# Double_Socket_NoPowersch.net
KiCad netlist of a schematic drawn in EAGLE
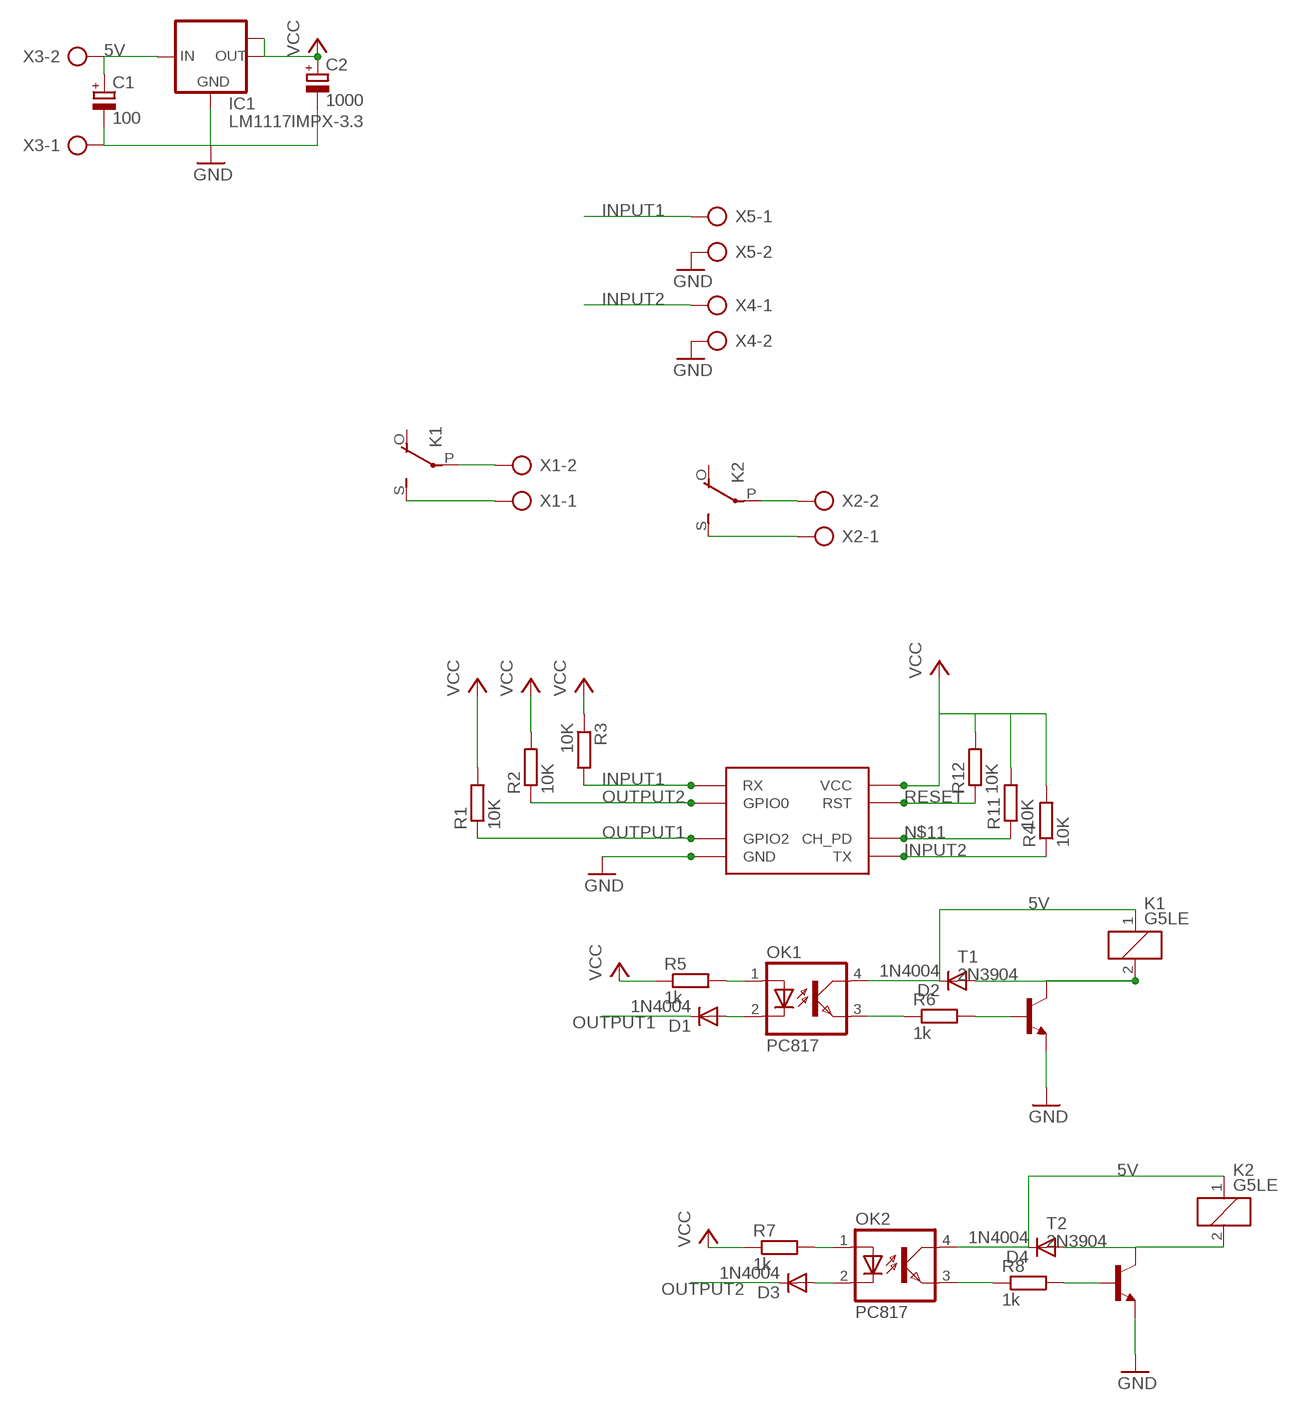
[diagram p0: schematic, sheet 1]

(export (version "E")
  (design (tool "Eeschema 10.0.6"))
  (components
    (comp (ref "C1")
      (value "100")
      (footprint "eagle-import:E5-10,5")
      (libsource (lib "eagle-import") (part "CPOL-EUE5-10.5"))
    )
    (comp (ref "C2")
      (value "1000")
      (footprint "eagle-import:E5-10,5")
      (libsource (lib "eagle-import") (part "CPOL-EUE5-10.5"))
    )
    (comp (ref "D1")
      (value "1N4004")
      (footprint "eagle-import:DO41-10")
      (libsource (lib "eagle-import") (part "1N4004"))
    )
    (comp (ref "D2")
      (value "1N4004")
      (footprint "eagle-import:DO41-10")
      (libsource (lib "eagle-import") (part "1N4004"))
    )
    (comp (ref "D3")
      (value "1N4004")
      (footprint "eagle-import:DO41-10")
      (libsource (lib "eagle-import") (part "1N4004"))
    )
    (comp (ref "D4")
      (value "1N4004")
      (footprint "eagle-import:DO41-10")
      (libsource (lib "eagle-import") (part "1N4004"))
    )
    (comp (ref "IC1")
      (value "LM1117IMPX-3.3")
      (footprint "eagle-import:SOT223")
      (libsource (lib "eagle-import") (part "LM1117IMPX-3.3"))
    )
    (comp (ref "K1")
      (value "G5LE")
      (footprint "eagle-import:G5LE")
      (libsource (lib "eagle-import") (part "G5LE"))
    )
    (comp (ref "K2")
      (value "G5LE")
      (footprint "eagle-import:G5LE")
      (libsource (lib "eagle-import") (part "G5LE"))
    )
    (comp (ref "OK1")
      (value "PC817")
      (footprint "eagle-import:DIL04")
      (fields (field (name "MPN") "PC817X4J000F"))
      (libsource (lib "eagle-import") (part "PC817"))
    )
    (comp (ref "OK2")
      (value "PC817")
      (footprint "eagle-import:DIL04")
      (fields (field (name "MPN") "PC817X4J000F"))
      (libsource (lib "eagle-import") (part "PC817"))
    )
    (comp (ref "R1")
      (value "10K")
      (footprint "eagle-import:0207_10")
      (libsource (lib "eagle-import") (part "R-EU_0207/10"))
    )
    (comp (ref "R2")
      (value "10K")
      (footprint "eagle-import:0207_10")
      (libsource (lib "eagle-import") (part "R-EU_0207/10"))
    )
    (comp (ref "R3")
      (value "10K")
      (footprint "eagle-import:0207_10")
      (libsource (lib "eagle-import") (part "R-EU_0207/10"))
    )
    (comp (ref "R4")
      (value "10K")
      (footprint "eagle-import:0207_10")
      (libsource (lib "eagle-import") (part "R-EU_0207/10"))
    )
    (comp (ref "R5")
      (value "1k")
      (footprint "eagle-import:0207_10")
      (libsource (lib "eagle-import") (part "R-EU_0207/10"))
    )
    (comp (ref "R6")
      (value "1k")
      (footprint "eagle-import:0207_10")
      (libsource (lib "eagle-import") (part "R-EU_0207/10"))
    )
    (comp (ref "R7")
      (value "1k")
      (footprint "eagle-import:0207_10")
      (libsource (lib "eagle-import") (part "R-EU_0207/10"))
    )
    (comp (ref "R8")
      (value "1k")
      (footprint "eagle-import:0207_10")
      (libsource (lib "eagle-import") (part "R-EU_0207/10"))
    )
    (comp (ref "R11")
      (value "10K")
      (footprint "eagle-import:0207_10")
      (libsource (lib "eagle-import") (part "R-EU_0207/10"))
    )
    (comp (ref "R12")
      (value "10K")
      (footprint "eagle-import:0207_10")
      (libsource (lib "eagle-import") (part "R-EU_0207/10"))
    )
    (comp (ref "T1")
      (value "2N3904")
      (footprint "eagle-import:TO92")
      (libsource (lib "eagle-import") (part "2N3904"))
    )
    (comp (ref "T2")
      (value "2N3904")
      (footprint "eagle-import:TO92")
      (libsource (lib "eagle-import") (part "2N3904"))
    )
    (comp (ref "U$2")
      (value "ESP8266")
      (footprint "eagle-import:ESP8266")
      (libsource (lib "eagle-import") (part "ESP8266"))
    )
    (comp (ref "X1")
      (value "AK500/2-H")
      (footprint "eagle-import:AK500_2-H")
      (libsource (lib "eagle-import") (part "AK500/2-H"))
    )
    (comp (ref "X2")
      (value "AK500/2-H")
      (footprint "eagle-import:AK500_2-H")
      (libsource (lib "eagle-import") (part "AK500/2-H"))
    )
    (comp (ref "X3")
      (value "AK500/2-H")
      (footprint "eagle-import:AK500_2-H")
      (libsource (lib "eagle-import") (part "AK500/2-H"))
    )
    (comp (ref "X4")
      (value "AK500/2-H")
      (footprint "eagle-import:AK500_2-H")
      (libsource (lib "eagle-import") (part "AK500/2-H"))
    )
    (comp (ref "X5")
      (value "AK500/2-H")
      (footprint "eagle-import:AK500_2-H")
      (libsource (lib "eagle-import") (part "AK500/2-H"))
    )
  )
  (nets
    (net (code "1") (name "/5V") (class "Default")
      (node (ref "C1") (pin "+") (pinfunction "+_+") (pintype "passive"))
      (node (ref "D2") (pin "C") (pinfunction "C_C") (pintype "passive"))
      (node (ref "D4") (pin "C") (pinfunction "C_C") (pintype "passive"))
      (node (ref "IC1") (pin "3") (pinfunction "IN_3") (pintype "input"))
      (node (ref "K1") (pin "1") (pinfunction "1_1") (pintype "passive"))
      (node (ref "K2") (pin "1") (pinfunction "1_1") (pintype "passive"))
      (node (ref "OK1") (pin "4") (pinfunction "COL_4") (pintype "passive"))
      (node (ref "OK2") (pin "4") (pinfunction "COL_4") (pintype "passive"))
      (node (ref "X3") (pin "2") (pinfunction "KL_2") (pintype "passive"))
    )
    (net (code "2") (name "/INPUT1") (class "Default")
      (node (ref "R3") (pin "2") (pinfunction "2_2") (pintype "passive"))
      (node (ref "U$2") (pin "RX") (pinfunction "RX_RX") (pintype "bidirectional"))
      (node (ref "X5") (pin "1") (pinfunction "KL_1") (pintype "passive"))
    )
    (net (code "3") (name "/INPUT2") (class "Default")
      (node (ref "R4") (pin "1") (pinfunction "1_1") (pintype "passive"))
      (node (ref "U$2") (pin "TX") (pinfunction "TX_TX") (pintype "bidirectional"))
      (node (ref "X4") (pin "1") (pinfunction "KL_1") (pintype "passive"))
    )
    (net (code "4") (name "/N$11") (class "Default")
      (node (ref "R11") (pin "1") (pinfunction "1_1") (pintype "passive"))
      (node (ref "U$2") (pin "CH_PD") (pinfunction "CH_PD_CH_PD") (pintype "bidirectional"))
    )
    (net (code "5") (name "/OUTPUT1") (class "Default")
      (node (ref "D1") (pin "C") (pinfunction "C_C") (pintype "passive"))
      (node (ref "R1") (pin "1") (pinfunction "1_1") (pintype "passive"))
      (node (ref "U$2") (pin "GPIO2") (pinfunction "GPIO2_GPIO2") (pintype "bidirectional"))
    )
    (net (code "6") (name "/OUTPUT2") (class "Default")
      (node (ref "D3") (pin "C") (pinfunction "C_C") (pintype "passive"))
      (node (ref "R2") (pin "1") (pinfunction "1_1") (pintype "passive"))
      (node (ref "U$2") (pin "GPIO0") (pinfunction "GPIO0_GPIO0") (pintype "bidirectional"))
    )
    (net (code "7") (name "/RESET") (class "Default")
      (node (ref "R12") (pin "1") (pinfunction "1_1") (pintype "passive"))
      (node (ref "U$2") (pin "RST") (pinfunction "RST_RST") (pintype "bidirectional"))
    )
    (net (code "8") (name "GND") (class "Default")
      (node (ref "C1") (pin "-") (pinfunction "-_-") (pintype "passive"))
      (node (ref "C2") (pin "-") (pinfunction "-_-") (pintype "passive"))
      (node (ref "IC1") (pin "1") (pinfunction "GND_1") (pintype "input"))
      (node (ref "T1") (pin "3") (pinfunction "E_3") (pintype "passive"))
      (node (ref "T2") (pin "3") (pinfunction "E_3") (pintype "passive"))
      (node (ref "U$2") (pin "GND") (pinfunction "GND_GND") (pintype "bidirectional"))
      (node (ref "X3") (pin "1") (pinfunction "KL_1") (pintype "passive"))
      (node (ref "X4") (pin "2") (pinfunction "KL_2") (pintype "passive"))
      (node (ref "X5") (pin "2") (pinfunction "KL_2") (pintype "passive"))
    )
    (net (code "9") (name "Net-(OK1-A)") (class "Default")
      (node (ref "OK1") (pin "1") (pinfunction "A_1") (pintype "passive"))
      (node (ref "R5") (pin "2") (pinfunction "2_2") (pintype "passive"))
    )
    (net (code "10") (name "Net-(OK1-C)") (class "Default")
      (node (ref "D1") (pin "A") (pinfunction "A_A") (pintype "passive"))
      (node (ref "OK1") (pin "2") (pinfunction "C_2") (pintype "passive"))
    )
    (net (code "11") (name "Net-(OK1-EMIT)") (class "Default")
      (node (ref "OK1") (pin "3") (pinfunction "EMIT_3") (pintype "passive"))
      (node (ref "R6") (pin "1") (pinfunction "1_1") (pintype "passive"))
    )
    (net (code "12") (name "Net-(OK2-A)") (class "Default")
      (node (ref "OK2") (pin "1") (pinfunction "A_1") (pintype "passive"))
      (node (ref "R7") (pin "2") (pinfunction "2_2") (pintype "passive"))
    )
    (net (code "13") (name "Net-(OK2-C)") (class "Default")
      (node (ref "D3") (pin "A") (pinfunction "A_A") (pintype "passive"))
      (node (ref "OK2") (pin "2") (pinfunction "C_2") (pintype "passive"))
    )
    (net (code "14") (name "Net-(OK2-EMIT)") (class "Default")
      (node (ref "OK2") (pin "3") (pinfunction "EMIT_3") (pintype "passive"))
      (node (ref "R8") (pin "1") (pinfunction "1_1") (pintype "passive"))
    )
    (net (code "15") (name "Net-(T1-B)") (class "Default")
      (node (ref "R6") (pin "2") (pinfunction "2_2") (pintype "passive"))
      (node (ref "T1") (pin "2") (pinfunction "B_2") (pintype "passive"))
    )
    (net (code "16") (name "Net-(T1-C)") (class "Default")
      (node (ref "D2") (pin "A") (pinfunction "A_A") (pintype "passive"))
      (node (ref "K1") (pin "2") (pinfunction "2_2") (pintype "passive"))
      (node (ref "T1") (pin "1") (pinfunction "C_1") (pintype "passive"))
    )
    (net (code "17") (name "Net-(T2-B)") (class "Default")
      (node (ref "R8") (pin "2") (pinfunction "2_2") (pintype "passive"))
      (node (ref "T2") (pin "2") (pinfunction "B_2") (pintype "passive"))
    )
    (net (code "18") (name "Net-(T2-C)") (class "Default")
      (node (ref "D4") (pin "A") (pinfunction "A_A") (pintype "passive"))
      (node (ref "K2") (pin "2") (pinfunction "2_2") (pintype "passive"))
      (node (ref "T2") (pin "1") (pinfunction "C_1") (pintype "passive"))
    )
    (net (code "19") (name "Net-(X1A-KL)") (class "Default")
      (node (ref "K1") (pin "S") (pinfunction "S_S") (pintype "passive"))
      (node (ref "X1") (pin "1") (pinfunction "KL_1") (pintype "passive"))
    )
    (net (code "20") (name "Net-(X1B-KL)") (class "Default")
      (node (ref "K1") (pin "P") (pinfunction "P_P") (pintype "passive"))
      (node (ref "X1") (pin "2") (pinfunction "KL_2") (pintype "passive"))
    )
    (net (code "21") (name "Net-(X2A-KL)") (class "Default")
      (node (ref "K2") (pin "S") (pinfunction "S_S") (pintype "passive"))
      (node (ref "X2") (pin "1") (pinfunction "KL_1") (pintype "passive"))
    )
    (net (code "22") (name "Net-(X2B-KL)") (class "Default")
      (node (ref "K2") (pin "P") (pinfunction "P_P") (pintype "passive"))
      (node (ref "X2") (pin "2") (pinfunction "KL_2") (pintype "passive"))
    )
    (net (code "23") (name "VCC") (class "Default")
      (node (ref "C2") (pin "+") (pinfunction "+_+") (pintype "passive"))
      (node (ref "IC1") (pin "2") (pinfunction "OUT_2") (pintype "passive"))
      (node (ref "IC1") (pin "TAB") (pinfunction "OUT1_TAB") (pintype "passive"))
      (node (ref "R1") (pin "2") (pinfunction "2_2") (pintype "passive"))
      (node (ref "R11") (pin "2") (pinfunction "2_2") (pintype "passive"))
      (node (ref "R12") (pin "2") (pinfunction "2_2") (pintype "passive"))
      (node (ref "R2") (pin "2") (pinfunction "2_2") (pintype "passive"))
      (node (ref "R3") (pin "1") (pinfunction "1_1") (pintype "passive"))
      (node (ref "R4") (pin "2") (pinfunction "2_2") (pintype "passive"))
      (node (ref "R5") (pin "1") (pinfunction "1_1") (pintype "passive"))
      (node (ref "R7") (pin "1") (pinfunction "1_1") (pintype "passive"))
      (node (ref "U$2") (pin "VCC") (pinfunction "VCC_VCC") (pintype "bidirectional"))
    )
    (net (code "24") (name "unconnected-(K1-PadO)") (class "Default")
      (node (ref "K1") (pin "O") (pinfunction "O_O") (pintype "passive"))
    )
    (net (code "25") (name "unconnected-(K2-PadO)") (class "Default")
      (node (ref "K2") (pin "O") (pinfunction "O_O") (pintype "passive"))
    )
  )
)
